# BTL-Sch.net
KiCad netlist of a schematic drawn in Altium Designer
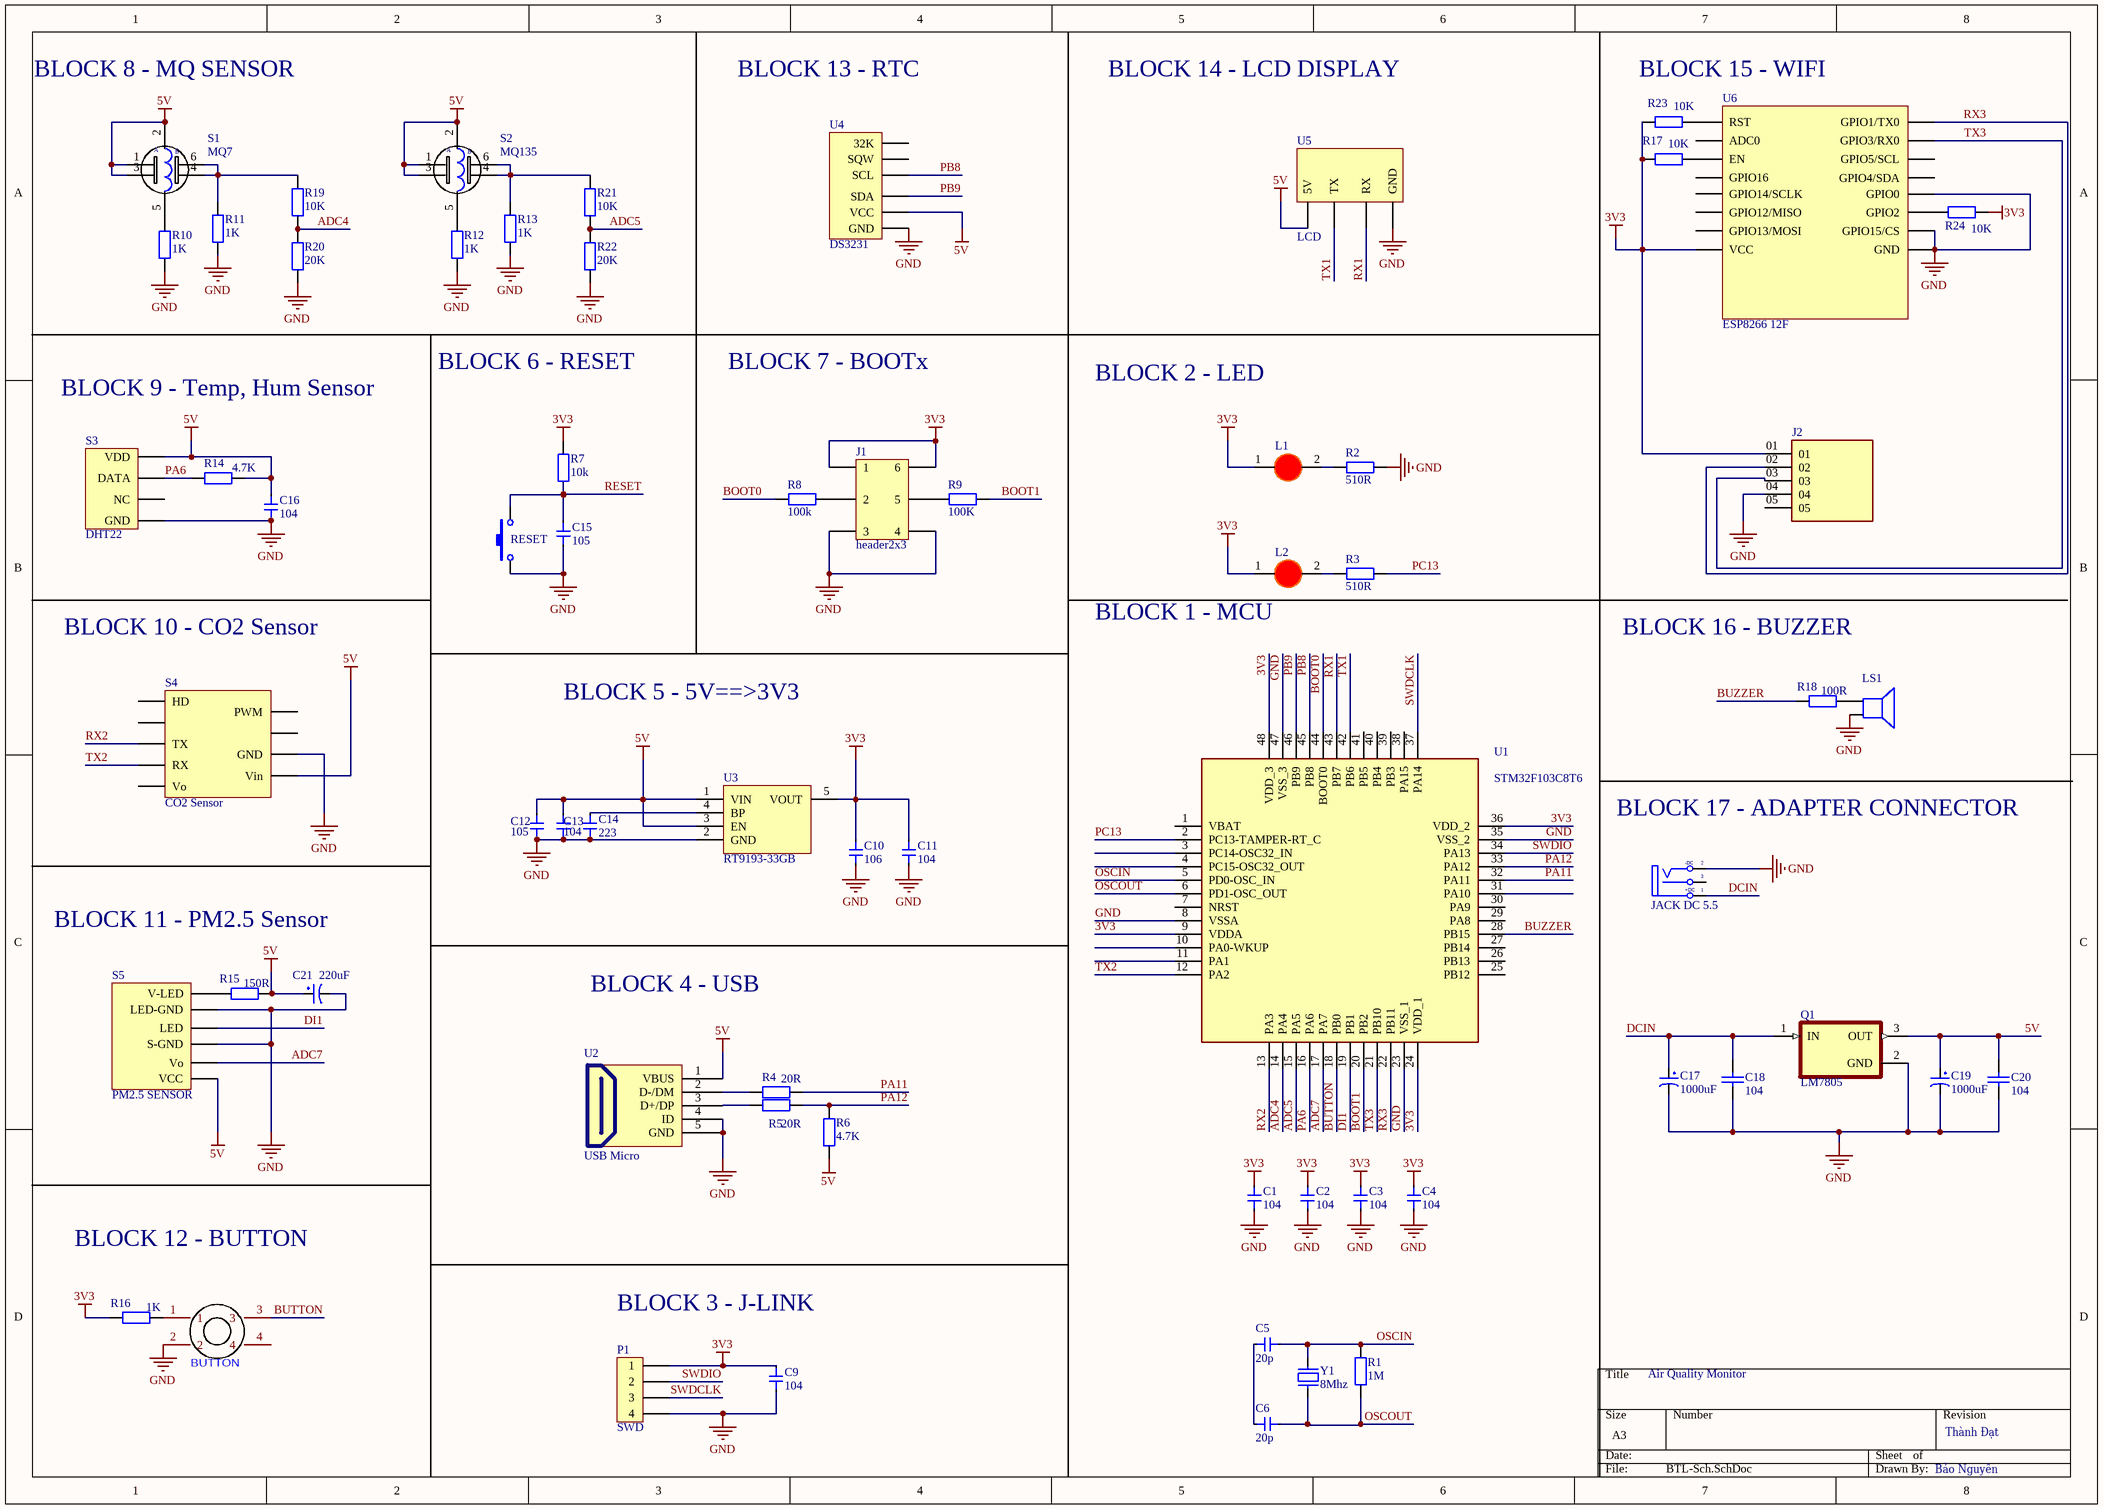
[diagram p0: BTL-Sch.SchDoc]

(export (version "E")
  (design (tool "Eeschema 10.0.6"))
  (components
    (comp (ref "BUTTON")
      (value "Nut Nhan 4 chan 12x12")
      (footprint "12X12 BUTTOM Blue")
      (libsource (lib "Altium_Lib_by_KhueNguyenCreator") (part "Nut Nhan 4 chan 12x12"))
    )
    (comp (ref "C1")
      (value "104")
      (footprint "Cap 0603")
      (description "Capacitor SMD 0603")
      (libsource (lib "Altium_Lib_by_KhueNguyenCreator") (part "Cap 0603"))
    )
    (comp (ref "C2")
      (value "104")
      (footprint "Cap 0603")
      (description "Capacitor SMD 0603")
      (libsource (lib "Altium_Lib_by_KhueNguyenCreator") (part "Cap 0603"))
    )
    (comp (ref "C3")
      (value "104")
      (footprint "Cap 0603")
      (description "Capacitor SMD 0603")
      (libsource (lib "Altium_Lib_by_KhueNguyenCreator") (part "Cap 0603"))
    )
    (comp (ref "C4")
      (value "104")
      (footprint "Cap 0603")
      (description "Capacitor SMD 0603")
      (libsource (lib "Altium_Lib_by_KhueNguyenCreator") (part "Cap 0603"))
    )
    (comp (ref "C5")
      (value "20p")
      (footprint "Cap 0603")
      (description "Capacitor SMD 0603")
      (libsource (lib "Altium_Lib_by_KhueNguyenCreator") (part "Cap 0603"))
    )
    (comp (ref "C6")
      (value "20p")
      (footprint "Cap 0603")
      (description "Capacitor SMD 0603")
      (libsource (lib "Altium_Lib_by_KhueNguyenCreator") (part "Cap 0603"))
    )
    (comp (ref "C9")
      (value "104")
      (footprint "Cap 0603")
      (description "Capacitor SMD 0603")
      (libsource (lib "Altium_Lib_by_KhueNguyenCreator") (part "Cap 0603"))
    )
    (comp (ref "C10")
      (value "106")
      (footprint "Cap 0805")
      (description "Capacitor SMD 0805")
      (libsource (lib "Altium_Lib_by_KhueNguyenCreator") (part "Cap 0805"))
    )
    (comp (ref "C11")
      (value "104")
      (footprint "Cap 0805")
      (description "Capacitor SMD 0805")
      (libsource (lib "Altium_Lib_by_KhueNguyenCreator") (part "Cap 0805"))
    )
    (comp (ref "C12")
      (value "105")
      (footprint "Cap 0805")
      (description "Capacitor SMD 0805")
      (libsource (lib "Altium_Lib_by_KhueNguyenCreator") (part "Cap 0805"))
    )
    (comp (ref "C13")
      (value "104")
      (footprint "Cap 0603")
      (description "Capacitor SMD 0603")
      (libsource (lib "Altium_Lib_by_KhueNguyenCreator") (part "Cap 0603"))
    )
    (comp (ref "C14")
      (value "223")
      (footprint "Cap 0603")
      (description "Capacitor SMD 0603")
      (libsource (lib "Altium_Lib_by_KhueNguyenCreator") (part "Cap 0603"))
    )
    (comp (ref "C15")
      (value "105")
      (footprint "Cap 0603")
      (description "Capacitor SMD 0603")
      (libsource (lib "Altium_Lib_by_KhueNguyenCreator") (part "Cap 0603"))
    )
    (comp (ref "C16")
      (value "104")
      (footprint "Cap 0603")
      (description "Capacitor SMD 0603")
      (libsource (lib "Altium_Lib_by_KhueNguyenCreator") (part "Cap 0603"))
    )
    (comp (ref "C17")
      (value "1000uF")
      (footprint "tu hoa 8mm")
      (description "Cắm")
      (libsource (lib "Altium_Lib_by_KhueNguyenCreator") (part "Tu Hoa 1000uF 16V 8x20"))
    )
    (comp (ref "C18")
      (value "104")
      (footprint "tu gom")
      (description "Cắm")
      (libsource (lib "Altium_Lib_by_KhueNguyenCreator") (part "Tu gom 104 50V"))
    )
    (comp (ref "C19")
      (value "1000uF")
      (footprint "tu hoa 8mm")
      (description "Cắm")
      (libsource (lib "Altium_Lib_by_KhueNguyenCreator") (part "Tu Hoa 1000uF 16V 8x20"))
    )
    (comp (ref "C20")
      (value "104")
      (footprint "tu gom")
      (description "Cắm")
      (libsource (lib "Altium_Lib_by_KhueNguyenCreator") (part "Tu gom 104 50V"))
    )
    (comp (ref "C21")
      (value "220uF")
      (footprint "tu hoa 5mm")
      (description "Cắm")
      (libsource (lib "Altium_Lib_by_KhueNguyenCreator") (part "Tu Hoa 220uF 10V 6x11"))
    )
    (comp (ref "J1")
      (value "header2x3")
      (footprint "header2x3")
      (libsource (lib "air_quality_monitor_lib") (part "header2x3"))
    )
    (comp (ref "J2")
      (value "MTSW-105-24-G-S-255")
      (footprint "SAMTEC_MTSW-105-24-G-S-255")
      (libsource (lib "header5pin") (part "MTSW-105-24-G-S-255"))
    )
    (comp (ref "JACK DC")
      (value "JACK DC 5.5")
      (footprint "JACK DC 5.5")
      (libsource (lib "Altium_Lib_by_KhueNguyenCreator") (part "JACK DC 5.5"))
    )
    (comp (ref "L1")
      (value "LED 0805")
      (footprint "LED-0805-Red")
      (description "Dán")
      (libsource (lib "Altium_Lib_by_KhueNguyenCreator") (part "LED 0805 Do"))
    )
    (comp (ref "L2")
      (value "LED 0805")
      (footprint "LED-0805-Red")
      (description "Dán")
      (libsource (lib "Altium_Lib_by_KhueNguyenCreator") (part "LED 0805 Do"))
    )
    (comp (ref "LS1")
      (value "Coi Chip Speaker")
      (footprint "Coi Chip Speacker")
      (description "Còi chip")
      (libsource (lib "Altium_Lib_by_KhueNguyenCreator") (part "Coi Chip Speaker"))
    )
    (comp (ref "P1")
      (value "SWD")
      (footprint "header4p_90")
      (libsource (lib "air_quality_monitor_lib") (part "header4p_90"))
    )
    (comp (ref "Q1")
      (value "LM7805")
      (footprint "TO254P1054X470X2600-3")
      (description "IC Regulator 7805T/LM7805T COMSET RoHS TO220")
      (fields (field (name "MP") "LM7805CT") (field (name "MF") "Comset Semiconductors"))
      (libsource (lib "LM7805") (part "LM7805"))
    )
    (comp (ref "R1")
      (value "1M")
      (footprint "tro smd 0603")
      (description "Dán")
      (libsource (lib "Altium_Lib_by_KhueNguyenCreator") (part "Tro 0603 1% 1k"))
    )
    (comp (ref "R2")
      (value "510R")
      (footprint "tro smd 0603")
      (description "Dán")
      (libsource (lib "Altium_Lib_by_KhueNguyenCreator") (part "Tro 0603 1% 10k"))
    )
    (comp (ref "R3")
      (value "510R")
      (footprint "tro smd 0603")
      (description "Dán")
      (libsource (lib "Altium_Lib_by_KhueNguyenCreator") (part "Tro 0603 1% 10k"))
    )
    (comp (ref "R4")
      (value "20R")
      (footprint "tro smd 0603")
      (description "Dán")
      (libsource (lib "Altium_Lib_by_KhueNguyenCreator") (part "Tro 0603 1% 1k"))
    )
    (comp (ref "R5")
      (value "20R")
      (footprint "tro smd 0603")
      (description "Dán")
      (libsource (lib "Altium_Lib_by_KhueNguyenCreator") (part "Tro 0603 1% 1k"))
    )
    (comp (ref "R6")
      (value "4.7K")
      (footprint "tro smd 0603")
      (description "Dán")
      (libsource (lib "Altium_Lib_by_KhueNguyenCreator") (part "Tro 0603 1% 1k"))
    )
    (comp (ref "R7")
      (value "10k")
      (footprint "tro smd 0603")
      (description "Dán")
      (libsource (lib "Altium_Lib_by_KhueNguyenCreator") (part "Tro 0603 1% 10k"))
    )
    (comp (ref "R8")
      (value "100k")
      (footprint "tro smd 0603")
      (description "Dán")
      (libsource (lib "Altium_Lib_by_KhueNguyenCreator") (part "Tro 0603 1% 10k"))
    )
    (comp (ref "R9")
      (value "100K")
      (footprint "tro smd 0603")
      (description "Dán")
      (libsource (lib "Altium_Lib_by_KhueNguyenCreator") (part "Tro 0603 1% 10k"))
    )
    (comp (ref "R10")
      (value "1K")
      (footprint "tro smd 0603")
      (description "Dán")
      (libsource (lib "Altium_Lib_by_KhueNguyenCreator") (part "Tro 0603 1% 10k"))
    )
    (comp (ref "R11")
      (value "1K")
      (footprint "tro smd 0603")
      (description "Dán")
      (libsource (lib "Altium_Lib_by_KhueNguyenCreator") (part "Tro 0603 1% 10k"))
    )
    (comp (ref "R12")
      (value "1K")
      (footprint "tro smd 0603")
      (description "Dán")
      (libsource (lib "Altium_Lib_by_KhueNguyenCreator") (part "Tro 0603 1% 10k"))
    )
    (comp (ref "R13")
      (value "1K")
      (footprint "tro smd 0603")
      (description "Dán")
      (libsource (lib "Altium_Lib_by_KhueNguyenCreator") (part "Tro 0603 1% 10k"))
    )
    (comp (ref "R14")
      (value "4.7K")
      (footprint "tro smd 0603")
      (description "Dán")
      (libsource (lib "Altium_Lib_by_KhueNguyenCreator") (part "Tro 0603 1% 10k"))
    )
    (comp (ref "R15")
      (value "150R")
      (footprint "tro smd 0603")
      (description "Dán")
      (libsource (lib "Altium_Lib_by_KhueNguyenCreator") (part "Tro 0603 1% 10k"))
    )
    (comp (ref "R16")
      (value "1K")
      (footprint "tro smd 0603")
      (description "Dán")
      (libsource (lib "Altium_Lib_by_KhueNguyenCreator") (part "Tro 0603 1% 10k"))
    )
    (comp (ref "R17")
      (value "10K")
      (footprint "tro smd 0603")
      (description "Dán")
      (libsource (lib "Altium_Lib_by_KhueNguyenCreator") (part "Tro 0603 1% 10k"))
    )
    (comp (ref "R18")
      (value "100R")
      (footprint "tro smd 0603")
      (description "Dán")
      (libsource (lib "Altium_Lib_by_KhueNguyenCreator") (part "Tro 0603 1% 10k"))
    )
    (comp (ref "R19")
      (value "10K")
      (footprint "tro smd 0603")
      (description "Dán")
      (libsource (lib "Altium_Lib_by_KhueNguyenCreator") (part "Tro 0603 1% 10k"))
    )
    (comp (ref "R20")
      (value "20K")
      (footprint "tro smd 0603")
      (description "Dán")
      (libsource (lib "Altium_Lib_by_KhueNguyenCreator") (part "Tro 0603 1% 10k"))
    )
    (comp (ref "R21")
      (value "10K")
      (footprint "tro smd 0603")
      (description "Dán")
      (libsource (lib "Altium_Lib_by_KhueNguyenCreator") (part "Tro 0603 1% 10k"))
    )
    (comp (ref "R22")
      (value "20K")
      (footprint "tro smd 0603")
      (description "Dán")
      (libsource (lib "Altium_Lib_by_KhueNguyenCreator") (part "Tro 0603 1% 10k"))
    )
    (comp (ref "R23")
      (value "10K")
      (footprint "tro smd 0603")
      (description "Dán")
      (libsource (lib "Altium_Lib_by_KhueNguyenCreator") (part "Tro 0603 1% 10k"))
    )
    (comp (ref "R24")
      (value "10K")
      (footprint "tro smd 0603")
      (description "Dán")
      (libsource (lib "Altium_Lib_by_KhueNguyenCreator") (part "Tro 0603 1% 10k"))
    )
    (comp (ref "RESET")
      (value "Nut Nhan 2 Chan SMD 3x6x2.5")
      (footprint "Nut Nhan 2 Chan SMD 3x6x2.5")
      (libsource (lib "Altium_Lib_by_KhueNguyenCreator") (part "Nut Nhan 2 Chan SMD 3x6x2.5"))
    )
    (comp (ref "S1") (value "MQ7") (footprint "mq7") (libsource (lib "air_quality_monitor_lib") (part "MQ7")))
    (comp (ref "S2")
      (value "MQ135")
      (footprint "mq135")
      (libsource (lib "air_quality_monitor_lib") (part "MQ135"))
    )
    (comp (ref "S3")
      (value "DHT22")
      (footprint "dht22")
      (libsource (lib "air_quality_monitor_lib") (part "DHT22"))
    )
    (comp (ref "S4")
      (value "CO2 Sensor")
      (footprint "co2sensor")
      (libsource (lib "air_quality_monitor_lib") (part "CO2 Sensor"))
    )
    (comp (ref "S5")
      (value "PM2.5 SENSOR")
      (footprint "pm25sensor")
      (libsource (lib "air_quality_monitor_lib") (part "PM2.5 SENSOR"))
    )
    (comp (ref "U1")
      (value "STM32F103C8T6")
      (footprint "LQFP-48_19.6_393_58X11_SMD")
      (description "ARM® Cortex®-M3 STM32F1 Microcontroller IC 32-Bit 72MHz 64KB (64K x 8) FLASH 48-LQFP (7x7)")
      (fields (field (name "MANUFACTURER") "STMicroelectronics"))
      (libsource (lib "Altium_Lib_by_KhueNguyenCreator") (part "IC_STM32F103C8T6"))
    )
    (comp (ref "U2")
      (value "USB Micro")
      (footprint "USB Micro 5p SMD")
      (description "USB Type B")
      (libsource (lib "Altium_Lib_by_KhueNguyenCreator") (part "USB Micro 5p SMD"))
    )
    (comp (ref "U3")
      (value "RT9193-33GB")
      (footprint "SOT23-5")
      (description "Linear Voltage Regulator IC 1 Output 300mA SOT-23-5")
      (fields (field (name "MANUFACTURER") "Richtek USA Inc."))
      (libsource (lib "Altium_Lib_by_KhueNguyenCreator") (part "REG_5.5V-3.3V-0.3A-1W-SOT-23-5"))
    )
    (comp (ref "U4")
      (value "DS3231")
      (footprint "DS3231")
      (libsource (lib "air_quality_monitor_lib") (part "DS3231"))
    )
    (comp (ref "U5") (value "LCD") (footprint "LCD") (libsource (lib "air_quality_monitor_lib") (part "LCD")))
    (comp (ref "U6")
      (value "ESP8266 12F")
      (footprint "ESP826612F")
      (libsource (lib "air_quality_monitor_lib") (part "ESP8266 12F"))
    )
    (comp (ref "Y1")
      (value "8Mhz")
      (footprint "Thach Anh 2 chan SMD")
      (description "Crystal For all Crystal 2pin.")
      (libsource (lib "Altium_Lib_by_KhueNguyenCreator") (part "Thach Anh 2 chan SMD"))
    )
  )
  (nets
    (net (code "1") (name "/ADC4") (class "Default")
      (node (ref "R19") (pin "1") (pinfunction "1_1") (pintype "passive"))
      (node (ref "R20") (pin "2") (pinfunction "2_2") (pintype "passive"))
      (node (ref "U1") (pin "14") (pinfunction "PA4_14") (pintype "passive"))
    )
    (net (code "2") (name "/ADC5") (class "Default")
      (node (ref "R21") (pin "1") (pinfunction "1_1") (pintype "passive"))
      (node (ref "R22") (pin "2") (pinfunction "2_2") (pintype "passive"))
      (node (ref "U1") (pin "15") (pinfunction "PA5_15") (pintype "passive"))
    )
    (net (code "3") (name "/ADC7") (class "Default")
      (node (ref "S5") (pin "5") (pinfunction "Vo_5") (pintype "passive"))
      (node (ref "U1") (pin "17") (pinfunction "PA7_17") (pintype "passive"))
    )
    (net (code "4") (name "/BOOT0") (class "Default")
      (node (ref "R8") (pin "2") (pinfunction "2_2") (pintype "passive"))
      (node (ref "U1") (pin "44") (pinfunction "BOOT0_44") (pintype "passive"))
    )
    (net (code "5") (name "/BOOT1") (class "Default")
      (node (ref "R9") (pin "1") (pinfunction "1_1") (pintype "passive"))
      (node (ref "U1") (pin "20") (pinfunction "PB2_20") (pintype "passive"))
    )
    (net (code "6") (name "/BUTTON") (class "Default")
      (node (ref "BUTTON") (pin "3") (pinfunction "3_3") (pintype "passive"))
      (node (ref "U1") (pin "18") (pinfunction "PB0_18") (pintype "passive"))
    )
    (net (code "7") (name "/BUZZER") (class "Default")
      (node (ref "R18") (pin "1") (pinfunction "1_1") (pintype "passive"))
      (node (ref "U1") (pin "28") (pinfunction "PB15_28") (pintype "passive"))
    )
    (net (code "8") (name "/DCIN") (class "Default")
      (node (ref "C17") (pin "1") (pinfunction "1_1") (pintype "passive"))
      (node (ref "C18") (pin "1") (pinfunction "1_1") (pintype "passive"))
      (node (ref "JACK DC") (pin "1") (pinfunction "T_1") (pintype "passive"))
      (node (ref "Q1") (pin "1") (pinfunction "IN_1") (pintype "input"))
    )
    (net (code "9") (name "/DI1") (class "Default")
      (node (ref "S5") (pin "3") (pinfunction "LED_3") (pintype "passive"))
      (node (ref "U1") (pin "19") (pinfunction "PB1_19") (pintype "passive"))
    )
    (net (code "10") (name "/OSCIN") (class "Default")
      (node (ref "C5") (pin "2") (pinfunction "2_2") (pintype "passive"))
      (node (ref "R1") (pin "2") (pinfunction "2_2") (pintype "passive"))
      (node (ref "U1") (pin "5") (pinfunction "PD0-OSC_IN_5") (pintype "passive"))
      (node (ref "Y1") (pin "2") (pinfunction "2_2") (pintype "passive"))
    )
    (net (code "11") (name "/OSCOUT") (class "Default")
      (node (ref "C6") (pin "2") (pinfunction "2_2") (pintype "passive"))
      (node (ref "R1") (pin "1") (pinfunction "1_1") (pintype "passive"))
      (node (ref "U1") (pin "6") (pinfunction "PD1-OSC_OUT_6") (pintype "passive"))
      (node (ref "Y1") (pin "1") (pinfunction "1_1") (pintype "passive"))
    )
    (net (code "12") (name "/PA6") (class "Default")
      (node (ref "R14") (pin "1") (pinfunction "1_1") (pintype "passive"))
      (node (ref "S3") (pin "2") (pinfunction "DATA_2") (pintype "passive"))
      (node (ref "U1") (pin "16") (pinfunction "PA6_16") (pintype "passive"))
    )
    (net (code "13") (name "/PA11") (class "Default")
      (node (ref "R4") (pin "1") (pinfunction "1_1") (pintype "passive"))
      (node (ref "U1") (pin "32") (pinfunction "PA11_32") (pintype "passive"))
    )
    (net (code "14") (name "/PA12") (class "Default")
      (node (ref "R5") (pin "1") (pinfunction "1_1") (pintype "passive"))
      (node (ref "R6") (pin "2") (pinfunction "2_2") (pintype "passive"))
      (node (ref "U1") (pin "33") (pinfunction "PA12_33") (pintype "passive"))
    )
    (net (code "15") (name "/PB8") (class "Default")
      (node (ref "U1") (pin "45") (pinfunction "PB8_45") (pintype "passive"))
      (node (ref "U4") (pin "3") (pinfunction "SCL_3") (pintype "passive"))
    )
    (net (code "16") (name "/PB9") (class "Default")
      (node (ref "U1") (pin "46") (pinfunction "PB9_46") (pintype "passive"))
      (node (ref "U4") (pin "4") (pinfunction "SDA_4") (pintype "passive"))
    )
    (net (code "17") (name "/PC13") (class "Default")
      (node (ref "R3") (pin "2") (pinfunction "2_2") (pintype "passive"))
      (node (ref "U1") (pin "2") (pinfunction "PC13-TAMPER-RT_C_2") (pintype "passive"))
    )
    (net (code "18") (name "/RESET") (class "Default")
      (node (ref "C15") (pin "1") (pinfunction "1_1") (pintype "passive"))
      (node (ref "R7") (pin "2") (pinfunction "2_2") (pintype "passive"))
      (node (ref "RESET") (pin "2") (pinfunction "2_2") (pintype "passive"))
    )
    (net (code "19") (name "/RX1") (class "Default")
      (node (ref "U1") (pin "43") (pinfunction "PB7_43") (pintype "passive"))
      (node (ref "U5") (pin "3") (pinfunction "RX_3") (pintype "passive"))
    )
    (net (code "20") (name "/RX2") (class "Default")
      (node (ref "S4") (pin "3") (pinfunction "TX_3") (pintype "passive"))
      (node (ref "U1") (pin "13") (pinfunction "PA3_13") (pintype "passive"))
    )
    (net (code "21") (name "/RX3") (class "Default")
      (node (ref "J2") (pin "02") (pinfunction "02_02") (pintype "passive"))
      (node (ref "U1") (pin "22") (pinfunction "PB11_22") (pintype "passive"))
      (node (ref "U6") (pin "22") (pinfunction "GPIO1/TX0_22") (pintype "passive"))
    )
    (net (code "22") (name "/SWDCLK") (class "Default")
      (node (ref "P1") (pin "3") (pinfunction "3_3") (pintype "passive"))
      (node (ref "U1") (pin "37") (pinfunction "PA14_37") (pintype "passive"))
    )
    (net (code "23") (name "/SWDIO") (class "Default")
      (node (ref "P1") (pin "2") (pinfunction "2_2") (pintype "passive"))
      (node (ref "U1") (pin "34") (pinfunction "PA13_34") (pintype "passive"))
    )
    (net (code "24") (name "/TX1") (class "Default")
      (node (ref "U1") (pin "42") (pinfunction "PB6_42") (pintype "passive"))
      (node (ref "U5") (pin "2") (pinfunction "TX_2") (pintype "passive"))
    )
    (net (code "25") (name "/TX2") (class "Default")
      (node (ref "S4") (pin "4") (pinfunction "RX_4") (pintype "passive"))
      (node (ref "U1") (pin "12") (pinfunction "PA2_12") (pintype "passive"))
    )
    (net (code "26") (name "/TX3") (class "Default")
      (node (ref "J2") (pin "03") (pinfunction "03_03") (pintype "passive"))
      (node (ref "U1") (pin "21") (pinfunction "PB10_21") (pintype "passive"))
      (node (ref "U6") (pin "21") (pinfunction "GPIO3/RX0_21") (pintype "passive"))
    )
    (net (code "27") (name "3V3") (class "Default")
      (node (ref "C1") (pin "1") (pinfunction "1_1") (pintype "passive"))
      (node (ref "C10") (pin "1") (pinfunction "1_1") (pintype "passive"))
      (node (ref "C11") (pin "1") (pinfunction "1_1") (pintype "passive"))
      (node (ref "C2") (pin "1") (pinfunction "1_1") (pintype "passive"))
      (node (ref "C3") (pin "1") (pinfunction "1_1") (pintype "passive"))
      (node (ref "C4") (pin "1") (pinfunction "1_1") (pintype "passive"))
      (node (ref "C9") (pin "1") (pinfunction "1_1") (pintype "passive"))
      (node (ref "J1") (pin "1") (pinfunction "1_1") (pintype "passive"))
      (node (ref "J1") (pin "6") (pinfunction "6_6") (pintype "passive"))
      (node (ref "J2") (pin "01") (pinfunction "01_01") (pintype "passive"))
      (node (ref "L1") (pin "1") (pinfunction "A_1") (pintype "passive"))
      (node (ref "L2") (pin "1") (pinfunction "A_1") (pintype "passive"))
      (node (ref "P1") (pin "1") (pinfunction "1_1") (pintype "passive"))
      (node (ref "R16") (pin "1") (pinfunction "1_1") (pintype "passive"))
      (node (ref "R17") (pin "1") (pinfunction "1_1") (pintype "passive"))
      (node (ref "R23") (pin "1") (pinfunction "1_1") (pintype "passive"))
      (node (ref "R24") (pin "2") (pinfunction "2_2") (pintype "passive"))
      (node (ref "R7") (pin "1") (pinfunction "1_1") (pintype "passive"))
      (node (ref "U1") (pin "24") (pinfunction "VDD_1_24") (pintype "passive"))
      (node (ref "U1") (pin "36") (pinfunction "VDD_2_36") (pintype "passive"))
      (node (ref "U1") (pin "48") (pinfunction "VDD_3_48") (pintype "passive"))
      (node (ref "U1") (pin "9") (pinfunction "VDDA_9") (pintype "passive"))
      (node (ref "U3") (pin "5") (pinfunction "VOUT_5") (pintype "passive"))
      (node (ref "U6") (pin "8") (pinfunction "VCC_8") (pintype "passive"))
    )
    (net (code "28") (name "5V") (class "Default")
      (node (ref "C12") (pin "1") (pinfunction "1_1") (pintype "passive"))
      (node (ref "C13") (pin "1") (pinfunction "1_1") (pintype "passive"))
      (node (ref "C16") (pin "1") (pinfunction "1_1") (pintype "passive"))
      (node (ref "C19") (pin "1") (pinfunction "1_1") (pintype "passive"))
      (node (ref "C20") (pin "1") (pinfunction "1_1") (pintype "passive"))
      (node (ref "C21") (pin "1") (pinfunction "1_1") (pintype "passive"))
      (node (ref "Q1") (pin "3") (pinfunction "OUT_3") (pintype "output"))
      (node (ref "R14") (pin "2") (pinfunction "2_2") (pintype "passive"))
      (node (ref "R15") (pin "2") (pinfunction "2_2") (pintype "passive"))
      (node (ref "R6") (pin "1") (pinfunction "1_1") (pintype "passive"))
      (node (ref "S1") (pin "1") (pinfunction "1_1") (pintype "passive"))
      (node (ref "S1") (pin "2") (pinfunction "2_2") (pintype "passive"))
      (node (ref "S1") (pin "3") (pinfunction "3_3") (pintype "passive"))
      (node (ref "S2") (pin "1") (pinfunction "1_1") (pintype "passive"))
      (node (ref "S2") (pin "2") (pinfunction "2_2") (pintype "passive"))
      (node (ref "S2") (pin "3") (pinfunction "3_3") (pintype "passive"))
      (node (ref "S3") (pin "1") (pinfunction "VDD_1") (pintype "passive"))
      (node (ref "S4") (pin "9") (pinfunction "Vin_9") (pintype "passive"))
      (node (ref "S5") (pin "6") (pinfunction "VCC_6") (pintype "passive"))
      (node (ref "U2") (pin "1") (pinfunction "VBUS_1") (pintype "passive"))
      (node (ref "U3") (pin "1") (pinfunction "VIN_1") (pintype "passive"))
      (node (ref "U3") (pin "3") (pinfunction "EN_3") (pintype "passive"))
      (node (ref "U4") (pin "5") (pinfunction "VCC_5") (pintype "passive"))
      (node (ref "U5") (pin "1") (pinfunction "5V_1") (pintype "passive"))
    )
    (net (code "29") (name "GND") (class "Default")
      (node (ref "BUTTON") (pin "2") (pinfunction "2_2") (pintype "passive"))
      (node (ref "C1") (pin "2") (pinfunction "2_2") (pintype "passive"))
      (node (ref "C10") (pin "2") (pinfunction "2_2") (pintype "passive"))
      (node (ref "C11") (pin "2") (pinfunction "2_2") (pintype "passive"))
      (node (ref "C12") (pin "2") (pinfunction "2_2") (pintype "passive"))
      (node (ref "C13") (pin "2") (pinfunction "2_2") (pintype "passive"))
      (node (ref "C14") (pin "2") (pinfunction "2_2") (pintype "passive"))
      (node (ref "C15") (pin "2") (pinfunction "2_2") (pintype "passive"))
      (node (ref "C16") (pin "2") (pinfunction "2_2") (pintype "passive"))
      (node (ref "C17") (pin "2") (pinfunction "2_2") (pintype "passive"))
      (node (ref "C18") (pin "2") (pinfunction "2_2") (pintype "passive"))
      (node (ref "C19") (pin "2") (pinfunction "2_2") (pintype "passive"))
      (node (ref "C2") (pin "2") (pinfunction "2_2") (pintype "passive"))
      (node (ref "C20") (pin "2") (pinfunction "2_2") (pintype "passive"))
      (node (ref "C21") (pin "2") (pinfunction "2_2") (pintype "passive"))
      (node (ref "C3") (pin "2") (pinfunction "2_2") (pintype "passive"))
      (node (ref "C4") (pin "2") (pinfunction "2_2") (pintype "passive"))
      (node (ref "C9") (pin "2") (pinfunction "2_2") (pintype "passive"))
      (node (ref "J1") (pin "3") (pinfunction "3_3") (pintype "passive"))
      (node (ref "J1") (pin "4") (pinfunction "4_4") (pintype "passive"))
      (node (ref "J2") (pin "04") (pinfunction "04_04") (pintype "passive"))
      (node (ref "JACK DC") (pin "2") (pinfunction "TN_2") (pintype "passive"))
      (node (ref "LS1") (pin "2") (pinfunction "2_2") (pintype "passive"))
      (node (ref "P1") (pin "4") (pinfunction "4_4") (pintype "passive"))
      (node (ref "Q1") (pin "2") (pinfunction "GND_2") (pintype "power_in"))
      (node (ref "R10") (pin "1") (pinfunction "1_1") (pintype "passive"))
      (node (ref "R11") (pin "2") (pinfunction "2_2") (pintype "passive"))
      (node (ref "R12") (pin "1") (pinfunction "1_1") (pintype "passive"))
      (node (ref "R13") (pin "2") (pinfunction "2_2") (pintype "passive"))
      (node (ref "R2") (pin "2") (pinfunction "2_2") (pintype "passive"))
      (node (ref "R20") (pin "1") (pinfunction "1_1") (pintype "passive"))
      (node (ref "R22") (pin "1") (pinfunction "1_1") (pintype "passive"))
      (node (ref "RESET") (pin "1") (pinfunction "1_1") (pintype "passive"))
      (node (ref "S3") (pin "4") (pinfunction "GND_4") (pintype "passive"))
      (node (ref "S4") (pin "8") (pinfunction "GND_8") (pintype "passive"))
      (node (ref "S5") (pin "2") (pinfunction "LED-GND_2") (pintype "passive"))
      (node (ref "S5") (pin "4") (pinfunction "S-GND_4") (pintype "passive"))
      (node (ref "U1") (pin "23") (pinfunction "VSS_1_23") (pintype "passive"))
      (node (ref "U1") (pin "35") (pinfunction "VSS_2_35") (pintype "passive"))
      (node (ref "U1") (pin "47") (pinfunction "VSS_3_47") (pintype "passive"))
      (node (ref "U1") (pin "8") (pinfunction "VSSA_8") (pintype "passive"))
      (node (ref "U2") (pin "4") (pinfunction "ID_4") (pintype "passive"))
      (node (ref "U2") (pin "5") (pinfunction "GND_5") (pintype "passive"))
      (node (ref "U3") (pin "2") (pinfunction "GND_2") (pintype "passive"))
      (node (ref "U4") (pin "6") (pinfunction "GND_6") (pintype "passive"))
      (node (ref "U5") (pin "4") (pinfunction "GND_4") (pintype "passive"))
      (node (ref "U6") (pin "15") (pinfunction "GND_15") (pintype "passive"))
      (node (ref "U6") (pin "16") (pinfunction "GPIO15/CS_16") (pintype "passive"))
      (node (ref "U6") (pin "18") (pinfunction "GPIO0_18") (pintype "passive"))
    )
    (net (code "30") (name "Net-(BUTTON-Pad1)") (class "Default")
      (node (ref "BUTTON") (pin "1") (pinfunction "1_1") (pintype "passive"))
      (node (ref "R16") (pin "2") (pinfunction "2_2") (pintype "passive"))
    )
    (net (code "31") (name "Net-(C5-Pad1)") (class "Default")
      (node (ref "C5") (pin "1") (pinfunction "1_1") (pintype "passive"))
      (node (ref "C6") (pin "1") (pinfunction "1_1") (pintype "passive"))
    )
    (net (code "32") (name "Net-(J1-Pad2)") (class "Default")
      (node (ref "J1") (pin "2") (pinfunction "2_2") (pintype "passive"))
      (node (ref "R8") (pin "1") (pinfunction "1_1") (pintype "passive"))
    )
    (net (code "33") (name "Net-(J1-Pad5)") (class "Default")
      (node (ref "J1") (pin "5") (pinfunction "5_5") (pintype "passive"))
      (node (ref "R9") (pin "2") (pinfunction "2_2") (pintype "passive"))
    )
    (net (code "34") (name "Net-(L1-K)") (class "Default")
      (node (ref "L1") (pin "2") (pinfunction "K_2") (pintype "passive"))
      (node (ref "R2") (pin "1") (pinfunction "1_1") (pintype "passive"))
    )
    (net (code "35") (name "Net-(L2-K)") (class "Default")
      (node (ref "L2") (pin "2") (pinfunction "K_2") (pintype "passive"))
      (node (ref "R3") (pin "1") (pinfunction "1_1") (pintype "passive"))
    )
    (net (code "36") (name "Net-(LS1-Pad1)") (class "Default")
      (node (ref "LS1") (pin "1") (pinfunction "1_1") (pintype "passive"))
      (node (ref "R18") (pin "2") (pinfunction "2_2") (pintype "passive"))
    )
    (net (code "37") (name "Net-(R10-Pad2)") (class "Default")
      (node (ref "R10") (pin "2") (pinfunction "2_2") (pintype "passive"))
      (node (ref "S1") (pin "5") (pinfunction "5_5") (pintype "passive"))
    )
    (net (code "38") (name "Net-(R11-Pad1)") (class "Default")
      (node (ref "R11") (pin "1") (pinfunction "1_1") (pintype "passive"))
      (node (ref "R19") (pin "2") (pinfunction "2_2") (pintype "passive"))
      (node (ref "S1") (pin "4") (pinfunction "4_4") (pintype "passive"))
      (node (ref "S1") (pin "6") (pinfunction "6_6") (pintype "passive"))
    )
    (net (code "39") (name "Net-(R12-Pad2)") (class "Default")
      (node (ref "R12") (pin "2") (pinfunction "2_2") (pintype "passive"))
      (node (ref "S2") (pin "5") (pinfunction "5_5") (pintype "passive"))
    )
    (net (code "40") (name "Net-(R13-Pad1)") (class "Default")
      (node (ref "R13") (pin "1") (pinfunction "1_1") (pintype "passive"))
      (node (ref "R21") (pin "2") (pinfunction "2_2") (pintype "passive"))
      (node (ref "S2") (pin "4") (pinfunction "4_4") (pintype "passive"))
      (node (ref "S2") (pin "6") (pinfunction "6_6") (pintype "passive"))
    )
    (net (code "41") (name "Net-(S5-V-LED)") (class "Default")
      (node (ref "R15") (pin "1") (pinfunction "1_1") (pintype "passive"))
      (node (ref "S5") (pin "1") (pinfunction "V-LED_1") (pintype "passive"))
    )
    (net (code "42") (name "Net-(U2-D+{slash}DP)") (class "Default")
      (node (ref "R5") (pin "2") (pinfunction "2_2") (pintype "passive"))
      (node (ref "U2") (pin "3") (pinfunction "D+/DP_3") (pintype "passive"))
    )
    (net (code "43") (name "Net-(U2-D-{slash}DM)") (class "Default")
      (node (ref "R4") (pin "2") (pinfunction "2_2") (pintype "passive"))
      (node (ref "U2") (pin "2") (pinfunction "D-/DM_2") (pintype "passive"))
    )
    (net (code "44") (name "Net-(U3-BP)") (class "Default")
      (node (ref "C14") (pin "1") (pinfunction "1_1") (pintype "passive"))
      (node (ref "U3") (pin "4") (pinfunction "BP_4") (pintype "passive"))
    )
    (net (code "45") (name "Net-(U6-EN)") (class "Default")
      (node (ref "R17") (pin "2") (pinfunction "2_2") (pintype "passive"))
      (node (ref "U6") (pin "3") (pinfunction "EN_3") (pintype "passive"))
    )
    (net (code "46") (name "Net-(U6-GPIO2)") (class "Default")
      (node (ref "R24") (pin "1") (pinfunction "1_1") (pintype "passive"))
      (node (ref "U6") (pin "17") (pinfunction "GPIO2_17") (pintype "passive"))
    )
    (net (code "47") (name "Net-(U6-RST)") (class "Default")
      (node (ref "R23") (pin "2") (pinfunction "2_2") (pintype "passive"))
      (node (ref "U6") (pin "1") (pinfunction "RST_1") (pintype "passive"))
    )
    (net (code "48") (name "unconnected-(BUTTON-Pad4)") (class "Default")
      (node (ref "BUTTON") (pin "4") (pinfunction "4_4") (pintype "passive"))
    )
    (net (code "49") (name "unconnected-(J2-Pad05)") (class "Default")
      (node (ref "J2") (pin "05") (pinfunction "05_05") (pintype "passive"))
    )
    (net (code "50") (name "unconnected-(JACK DC-S-Pad3)") (class "Default")
      (node (ref "JACK DC") (pin "3") (pinfunction "S_3") (pintype "power_in"))
    )
    (net (code "51") (name "unconnected-(S3-NC-Pad3)") (class "Default")
      (node (ref "S3") (pin "3") (pinfunction "NC_3") (pintype "passive"))
    )
    (net (code "52") (name "unconnected-(S4-HD-Pad1)") (class "Default")
      (node (ref "S4") (pin "1") (pinfunction "HD_1") (pintype "passive"))
    )
    (net (code "53") (name "unconnected-(S4-PWM-Pad6)") (class "Default")
      (node (ref "S4") (pin "6") (pinfunction "PWM_6") (pintype "passive"))
    )
    (net (code "54") (name "unconnected-(S4-Pad2)") (class "Default")
      (node (ref "S4") (pin "2") (pinfunction "2_2") (pintype "passive"))
    )
    (net (code "55") (name "unconnected-(S4-Pad7)") (class "Default")
      (node (ref "S4") (pin "7") (pinfunction "7_7") (pintype "passive"))
    )
    (net (code "56") (name "unconnected-(S4-Vo-Pad5)") (class "Default")
      (node (ref "S4") (pin "5") (pinfunction "Vo_5") (pintype "passive"))
    )
    (net (code "57") (name "unconnected-(U1-NRST-Pad7)") (class "Default")
      (node (ref "U1") (pin "7") (pinfunction "NRST_7") (pintype "passive"))
    )
    (net (code "58") (name "unconnected-(U1-PA0-WKUP-Pad10)") (class "Default")
      (node (ref "U1") (pin "10") (pinfunction "PA0-WKUP_10") (pintype "passive"))
    )
    (net (code "59") (name "unconnected-(U1-PA1-Pad11)") (class "Default")
      (node (ref "U1") (pin "11") (pinfunction "PA1_11") (pintype "passive"))
    )
    (net (code "60") (name "unconnected-(U1-PA8-Pad29)") (class "Default")
      (node (ref "U1") (pin "29") (pinfunction "PA8_29") (pintype "passive"))
    )
    (net (code "61") (name "unconnected-(U1-PA9-Pad30)") (class "Default")
      (node (ref "U1") (pin "30") (pinfunction "PA9_30") (pintype "passive"))
    )
    (net (code "62") (name "unconnected-(U1-PA10-Pad31)") (class "Default")
      (node (ref "U1") (pin "31") (pinfunction "PA10_31") (pintype "passive"))
    )
    (net (code "63") (name "unconnected-(U1-PA15-Pad38)") (class "Default")
      (node (ref "U1") (pin "38") (pinfunction "PA15_38") (pintype "passive"))
    )
    (net (code "64") (name "unconnected-(U1-PB3-Pad39)") (class "Default")
      (node (ref "U1") (pin "39") (pinfunction "PB3_39") (pintype "passive"))
    )
    (net (code "65") (name "unconnected-(U1-PB4-Pad40)") (class "Default")
      (node (ref "U1") (pin "40") (pinfunction "PB4_40") (pintype "passive"))
    )
    (net (code "66") (name "unconnected-(U1-PB5-Pad41)") (class "Default")
      (node (ref "U1") (pin "41") (pinfunction "PB5_41") (pintype "passive"))
    )
    (net (code "67") (name "unconnected-(U1-PB12-Pad25)") (class "Default")
      (node (ref "U1") (pin "25") (pinfunction "PB12_25") (pintype "passive"))
    )
    (net (code "68") (name "unconnected-(U1-PB13-Pad26)") (class "Default")
      (node (ref "U1") (pin "26") (pinfunction "PB13_26") (pintype "passive"))
    )
    (net (code "69") (name "unconnected-(U1-PB14-Pad27)") (class "Default")
      (node (ref "U1") (pin "27") (pinfunction "PB14_27") (pintype "passive"))
    )
    (net (code "70") (name "unconnected-(U1-PC14-OSC32_IN-Pad3)") (class "Default")
      (node (ref "U1") (pin "3") (pinfunction "PC14-OSC32_IN_3") (pintype "passive"))
    )
    (net (code "71") (name "unconnected-(U1-PC15-OSC32_OUT-Pad4)") (class "Default")
      (node (ref "U1") (pin "4") (pinfunction "PC15-OSC32_OUT_4") (pintype "passive"))
    )
    (net (code "72") (name "unconnected-(U1-VBAT-Pad1)") (class "Default")
      (node (ref "U1") (pin "1") (pinfunction "VBAT_1") (pintype "passive"))
    )
    (net (code "73") (name "unconnected-(U4-32K-Pad1)") (class "Default")
      (node (ref "U4") (pin "1") (pinfunction "32K_1") (pintype "passive"))
    )
    (net (code "74") (name "unconnected-(U4-SQW-Pad2)") (class "Default")
      (node (ref "U4") (pin "2") (pinfunction "SQW_2") (pintype "passive"))
    )
    (net (code "75") (name "unconnected-(U6-ADC0-Pad2)") (class "Default")
      (node (ref "U6") (pin "2") (pinfunction "ADC0_2") (pintype "passive"))
    )
    (net (code "76") (name "unconnected-(U6-GPIO4{slash}SDA-Pad19)") (class "Default")
      (node (ref "U6") (pin "19") (pinfunction "GPIO4/SDA_19") (pintype "passive"))
    )
    (net (code "77") (name "unconnected-(U6-GPIO5{slash}SCL-Pad20)") (class "Default")
      (node (ref "U6") (pin "20") (pinfunction "GPIO5/SCL_20") (pintype "passive"))
    )
    (net (code "78") (name "unconnected-(U6-GPIO12{slash}MISO-Pad6)") (class "Default")
      (node (ref "U6") (pin "6") (pinfunction "GPIO12/MISO_6") (pintype "passive"))
    )
    (net (code "79") (name "unconnected-(U6-GPIO13{slash}MOSI-Pad7)") (class "Default")
      (node (ref "U6") (pin "7") (pinfunction "GPIO13/MOSI_7") (pintype "passive"))
    )
    (net (code "80") (name "unconnected-(U6-GPIO14{slash}SCLK-Pad1)") (class "Default")
      (node (ref "U6") (pin "1") (pinfunction "GPIO14/SCLK_1") (pintype "passive"))
    )
    (net (code "81") (name "unconnected-(U6-GPIO16-Pad4)") (class "Default")
      (node (ref "U6") (pin "4") (pinfunction "GPIO16_4") (pintype "passive"))
    )
  )
)
